# power.net
KiCad netlist of a schematic drawn in Altium Designer
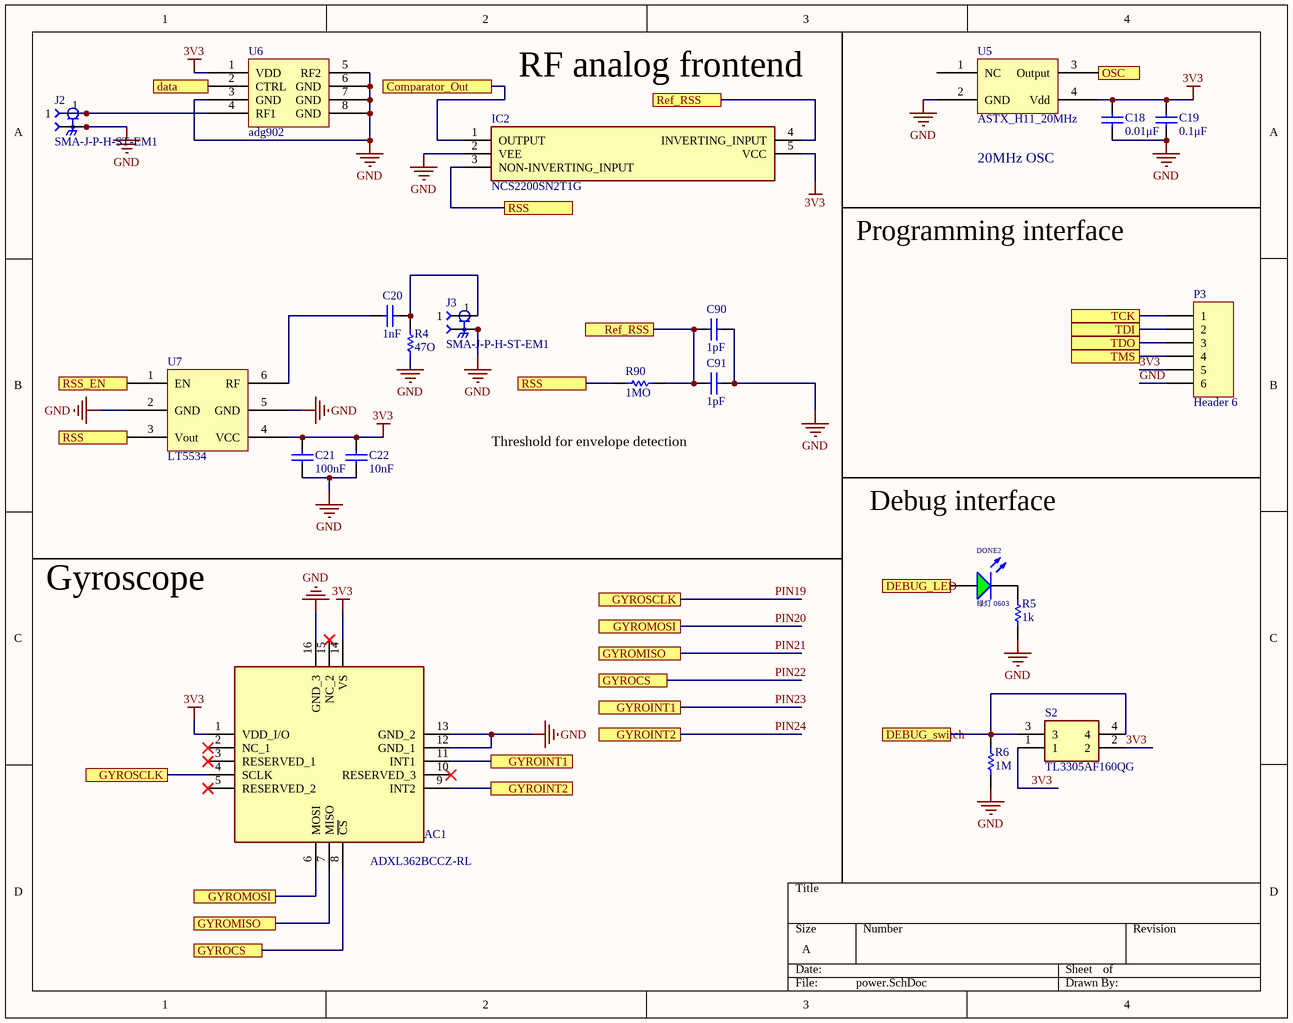
[diagram p0: power.SchDoc]

(export (version "E")
  (design (tool "Eeschema 10.0.6"))
  (components
    (comp (ref "AC1")
      (value "ADXL362BCCZ-RL")
      (footprint "SamacSys:ADXL362BCCZRL")
      (description "Accelerometer")
      (fields (field (name "MOUSER2 PART NUMBER") "584-ADXL362BCCZ-R"))
      (libsource (lib "*") (part "ADXL362BCCZ-RL"))
    )
    (comp (ref "C18")
      (value "0.01μF")
      (footprint "1608[0603]")
      (description "MLCCs")
      (fields (field (name "PUBLISHER") "Altium Limited"))
      (libsource (lib "Passer") (part "CAP_3"))
    )
    (comp (ref "C19")
      (value "0.1μF")
      (footprint "1608[0603]")
      (description "MLCCs")
      (fields (field (name "PUBLISHER") "Altium Limited"))
      (libsource (lib "Passer") (part "CAP_2"))
    )
    (comp (ref "C20")
      (value "1nF")
      (footprint "1608[0603]")
      (description "Ceramic Capacitor (Surface Mount)")
      (fields (field (name "MANUFACTURER") "Generic Ceramic Chip Cap (TBD)"))
      (libsource (lib "wisp") (part "Cap"))
    )
    (comp (ref "C21")
      (value "100nF")
      (footprint "1608[0603]")
      (description "Ceramic Capacitor (Surface Mount)")
      (fields (field (name "MANUFACTURER") "Generic Ceramic Chip Cap (TBD)"))
      (libsource (lib "wisp") (part "Cap"))
    )
    (comp (ref "C22")
      (value "10nF")
      (footprint "1608[0603]")
      (description "Ceramic Capacitor (Surface Mount)")
      (fields (field (name "MANUFACTURER") "Generic Ceramic Chip Cap (TBD)"))
      (libsource (lib "wisp") (part "Cap"))
    )
    (comp (ref "C90")
      (value "1pF")
      (footprint "1608[0603]")
      (description "Ceramic Capacitor (Surface Mount)")
      (fields (field (name "MANUFACTURER") "Generic Ceramic Chip Cap (TBD)") (field (name "Comment") "1nF"))
      (libsource (lib "wisp") (part "Cap"))
    )
    (comp (ref "C91")
      (value "1pF")
      (footprint "1608[0603]")
      (description "Ceramic Capacitor (Surface Mount)")
      (fields (field (name "MANUFACTURER") "Generic Ceramic Chip Cap (TBD)") (field (name "Comment") "1nF"))
      (libsource (lib "wisp") (part "Cap"))
    )
    (comp (ref "DONE2")
      (value "绿灯 0603")
      (footprint "0603_LED")
      (description "发光二极管")
      (libsource (lib "Passer") (part "0603 绿灯"))
    )
    (comp (ref "IC2")
      (value "NCS2200SN2T1G")
      (footprint "SamacSys:SOT95P275X110-5N")
      (description "Integrated Circuit")
      (libsource (lib "ComparatorLib") (part "NCS2200SN2T1G"))
    )
    (comp (ref "J2")
      (value "SMA-J-P-H-ST-EM1")
      (footprint "SAMTEC_SMA-J-P-H-ST-EM1")
      (description "SMA Connector Jack, Female Socket 50Ohm Board Edge, End Launch Solder")
      (fields (field (name "MF") "Samtec") (field (name "DIGI-KEY_PART_NUMBER") "SAM8857-ND"))
      (libsource (lib "SMA-J-P-H-ST-EM1") (part "SMA-J-P-H-ST-EM1"))
    )
    (comp (ref "J3")
      (value "SMA-J-P-H-ST-EM1")
      (footprint "SAMTEC_SMA-J-P-H-ST-EM1")
      (description "SMA Connector Jack, Female Socket 50Ohm Board Edge, End Launch Solder")
      (fields (field (name "MF") "Samtec") (field (name "DIGI-KEY_PART_NUMBER") "SAM8857-ND"))
      (libsource (lib "SMA-J-P-H-ST-EM1") (part "SMA-J-P-H-ST-EM1"))
    )
    (comp (ref "P3")
      (value "Header 6")
      (footprint "HDR1X6")
      (description "Header, 6-Pin")
      (fields (field (name "PUBLISHER") "Altium Limited"))
      (libsource (lib "Miscellaneous Connectors") (part "Header 6"))
    )
    (comp (ref "R4")
      (value "47O")
      (footprint "1608[0603]")
      (description "Chip Resistor (Surface Mount)")
      (fields (field (name "MANUFACTURER") "Generic Chip Res (TBD)") (field (name "Comment") "47 Ohm"))
      (libsource (lib "wisp") (part "Res"))
    )
    (comp (ref "R5")
      (value "1k")
      (footprint "1608[0603]")
      (description "Chip Resistor (Surface Mount)")
      (fields (field (name "MANUFACTURER") "Generic Chip Res (TBD)") (field (name "Comment") "1k Ohm"))
      (libsource (lib "wisp") (part "Res"))
    )
    (comp (ref "R6")
      (value "1M")
      (footprint "1608[0603]")
      (description "Chip Resistor (Surface Mount)")
      (fields (field (name "MANUFACTURER") "Generic Chip Res (TBD)") (field (name "Comment") "1k Ohm"))
      (libsource (lib "wisp") (part "Res"))
    )
    (comp (ref "R90")
      (value "1MO")
      (footprint "1608[0603]")
      (description "Chip Resistor (Surface Mount)")
      (fields (field (name "MANUFACTURER") "Generic Chip Res (TBD)") (field (name "Comment") "47 Ohm"))
      (libsource (lib "wisp") (part "Res"))
    )
    (comp (ref "S2")
      (value "TL3305AF160QG")
      (footprint "TL3305AF160QG")
      (description "Switch")
      (fields (field (name "MOUSER2 PART NUMBER") "612-TL3305AF160QG"))
      (libsource (lib "*") (part "TL3305AF160QG"))
    )
    (comp (ref "U5")
      (value "ASTX_H11_20MHz")
      (footprint "ASTX_H11")
      (libsource (lib "pengyulib") (part "ASTX_H11_20MHz"))
    )
    (comp (ref "U6") (value "adg902") (footprint "ADG902") (libsource (lib "pengyulib") (part "adg902")))
    (comp (ref "U7") (value "LT5534") (footprint "LT5534") (libsource (lib "pengyulib") (part "LT55534")))
  )
  (nets
    (net (code "1") (name "/Comparator_Out") (class "Default")
      (node (ref "IC2") (pin "1") (pinfunction "OUTPUT_1") (pintype "passive"))
    )
    (net (code "2") (name "/DEBUG_LED") (class "Default")
      (node (ref "DONE2") (pin "A") (pinfunction "A_A") (pintype "passive"))
    )
    (net (code "3") (name "/DEBUG_switch") (class "Default")
      (node (ref "R6") (pin "2") (pinfunction "2_2") (pintype "passive"))
      (node (ref "S2") (pin "3") (pinfunction "3_3") (pintype "passive"))
      (node (ref "S2") (pin "4") (pinfunction "4_4") (pintype "passive"))
    )
    (net (code "4") (name "/OSC") (class "Default")
      (node (ref "U5") (pin "3") (pinfunction "Output_3") (pintype "passive"))
    )
    (net (code "5") (name "/PIN19") (class "Default")
      (node (ref "AC1") (pin "4") (pinfunction "SCLK_4") (pintype "passive"))
    )
    (net (code "6") (name "/PIN20") (class "Default")
      (node (ref "AC1") (pin "6") (pinfunction "MOSI_6") (pintype "passive"))
    )
    (net (code "7") (name "/PIN21") (class "Default")
      (node (ref "AC1") (pin "7") (pinfunction "MISO_7") (pintype "passive"))
    )
    (net (code "8") (name "/PIN22") (class "Default")
      (node (ref "AC1") (pin "8") (pinfunction "~{CS}_8") (pintype "passive"))
    )
    (net (code "9") (name "/PIN23") (class "Default")
      (node (ref "AC1") (pin "11") (pinfunction "INT1_11") (pintype "passive"))
    )
    (net (code "10") (name "/PIN24") (class "Default")
      (node (ref "AC1") (pin "9") (pinfunction "INT2_9") (pintype "passive"))
    )
    (net (code "11") (name "/RSS") (class "Default")
      (node (ref "IC2") (pin "3") (pinfunction "NON-INVERTING_INPUT_3") (pintype "passive"))
      (node (ref "R90") (pin "2") (pinfunction "2_2") (pintype "passive"))
      (node (ref "U7") (pin "3") (pinfunction "Vout_3") (pintype "passive"))
    )
    (net (code "12") (name "/RSS_EN") (class "Default")
      (node (ref "U7") (pin "1") (pinfunction "EN_1") (pintype "passive"))
    )
    (net (code "13") (name "/Ref_RSS") (class "Default")
      (node (ref "C90") (pin "1") (pinfunction "1_1") (pintype "passive"))
      (node (ref "C91") (pin "1") (pinfunction "1_1") (pintype "passive"))
      (node (ref "IC2") (pin "4") (pinfunction "INVERTING_INPUT_4") (pintype "passive"))
      (node (ref "R90") (pin "1") (pinfunction "1_1") (pintype "passive"))
    )
    (net (code "14") (name "/TCK") (class "Default")
      (node (ref "P3") (pin "1") (pinfunction "1_1") (pintype "passive"))
    )
    (net (code "15") (name "/TDI") (class "Default")
      (node (ref "P3") (pin "2") (pinfunction "2_2") (pintype "passive"))
    )
    (net (code "16") (name "/TDO") (class "Default")
      (node (ref "P3") (pin "3") (pinfunction "3_3") (pintype "passive"))
    )
    (net (code "17") (name "/TMS") (class "Default")
      (node (ref "P3") (pin "4") (pinfunction "4_4") (pintype "passive"))
    )
    (net (code "18") (name "/data") (class "Default")
      (node (ref "U6") (pin "2") (pinfunction "CTRL_2") (pintype "passive"))
    )
    (net (code "19") (name "3V3") (class "Default")
      (node (ref "AC1") (pin "1") (pinfunction "VDD_I/O_1") (pintype "passive"))
      (node (ref "AC1") (pin "14") (pinfunction "VS_14") (pintype "passive"))
      (node (ref "C18") (pin "2") (pinfunction "2_2") (pintype "passive"))
      (node (ref "C19") (pin "2") (pinfunction "2_2") (pintype "passive"))
      (node (ref "C21") (pin "2") (pinfunction "2_2") (pintype "passive"))
      (node (ref "C22") (pin "2") (pinfunction "2_2") (pintype "passive"))
      (node (ref "IC2") (pin "5") (pinfunction "VCC_5") (pintype "passive"))
      (node (ref "P3") (pin "5") (pinfunction "5_5") (pintype "passive"))
      (node (ref "S2") (pin "1") (pinfunction "1_1") (pintype "passive"))
      (node (ref "S2") (pin "2") (pinfunction "2_2") (pintype "passive"))
      (node (ref "U5") (pin "4") (pinfunction "Vdd_4") (pintype "passive"))
      (node (ref "U6") (pin "1") (pinfunction "VDD_1") (pintype "passive"))
      (node (ref "U7") (pin "4") (pinfunction "VCC_4") (pintype "passive"))
    )
    (net (code "20") (name "GND") (class "Default")
      (node (ref "AC1") (pin "12") (pinfunction "GND_1_12") (pintype "passive"))
      (node (ref "AC1") (pin "13") (pinfunction "GND_2_13") (pintype "passive"))
      (node (ref "AC1") (pin "16") (pinfunction "GND_3_16") (pintype "passive"))
      (node (ref "C18") (pin "1") (pinfunction "1_1") (pintype "passive"))
      (node (ref "C19") (pin "1") (pinfunction "1_1") (pintype "passive"))
      (node (ref "C21") (pin "1") (pinfunction "1_1") (pintype "passive"))
      (node (ref "C22") (pin "1") (pinfunction "1_1") (pintype "passive"))
      (node (ref "C90") (pin "2") (pinfunction "2_2") (pintype "passive"))
      (node (ref "C91") (pin "2") (pinfunction "2_2") (pintype "passive"))
      (node (ref "IC2") (pin "2") (pinfunction "VEE_2") (pintype "passive"))
      (node (ref "J2") (pin "2_1") (pinfunction "2_2_1") (pintype "passive"))
      (node (ref "J2") (pin "2_2") (pinfunction "2_2_2") (pintype "passive"))
      (node (ref "J2") (pin "3_1") (pinfunction "2_3_1") (pintype "passive"))
      (node (ref "J2") (pin "3_2") (pinfunction "2_3_2") (pintype "passive"))
      (node (ref "J3") (pin "2_1") (pinfunction "2_2_1") (pintype "passive"))
      (node (ref "J3") (pin "2_2") (pinfunction "2_2_2") (pintype "passive"))
      (node (ref "J3") (pin "3_1") (pinfunction "2_3_1") (pintype "passive"))
      (node (ref "J3") (pin "3_2") (pinfunction "2_3_2") (pintype "passive"))
      (node (ref "P3") (pin "6") (pinfunction "6_6") (pintype "passive"))
      (node (ref "R4") (pin "1") (pinfunction "1_1") (pintype "passive"))
      (node (ref "R5") (pin "1") (pinfunction "1_1") (pintype "passive"))
      (node (ref "R6") (pin "1") (pinfunction "1_1") (pintype "passive"))
      (node (ref "U5") (pin "2") (pinfunction "GND_2") (pintype "passive"))
      (node (ref "U6") (pin "3") (pinfunction "GND_3") (pintype "passive"))
      (node (ref "U6") (pin "5") (pinfunction "RF2_5") (pintype "passive"))
      (node (ref "U6") (pin "6") (pinfunction "GND_6") (pintype "passive"))
      (node (ref "U6") (pin "7") (pinfunction "GND_7") (pintype "passive"))
      (node (ref "U6") (pin "8") (pinfunction "GND_8") (pintype "passive"))
      (node (ref "U7") (pin "2") (pinfunction "GND_2") (pintype "passive"))
      (node (ref "U7") (pin "5") (pinfunction "GND_5") (pintype "passive"))
    )
    (net (code "21") (name "Net-(C20-Pad2)") (class "Default")
      (node (ref "C20") (pin "2") (pinfunction "2_2") (pintype "passive"))
      (node (ref "J3") (pin "1") (pinfunction "1_1") (pintype "passive"))
      (node (ref "R4") (pin "2") (pinfunction "2_2") (pintype "passive"))
    )
    (net (code "22") (name "Net-(DONE2-PadK)") (class "Default")
      (node (ref "DONE2") (pin "K") (pinfunction "K_K") (pintype "passive"))
      (node (ref "R5") (pin "2") (pinfunction "2_2") (pintype "passive"))
    )
    (net (code "23") (name "Net-(U6-RF1)") (class "Default")
      (node (ref "J2") (pin "1") (pinfunction "1_1") (pintype "passive"))
      (node (ref "U6") (pin "4") (pinfunction "RF1_4") (pintype "passive"))
    )
    (net (code "24") (name "Net-(U7-RF)") (class "Default")
      (node (ref "C20") (pin "1") (pinfunction "1_1") (pintype "passive"))
      (node (ref "U7") (pin "6") (pinfunction "RF_6") (pintype "passive"))
    )
    (net (code "25") (name "unconnected-(AC1-NC_1-Pad2)") (class "Default")
      (node (ref "AC1") (pin "2") (pinfunction "NC_1_2") (pintype "passive+no_connect"))
    )
    (net (code "26") (name "unconnected-(AC1-NC_2-Pad15)") (class "Default")
      (node (ref "AC1") (pin "15") (pinfunction "NC_2_15") (pintype "passive+no_connect"))
    )
    (net (code "27") (name "unconnected-(AC1-RESERVED_1-Pad3)") (class "Default")
      (node (ref "AC1") (pin "3") (pinfunction "RESERVED_1_3") (pintype "passive+no_connect"))
    )
    (net (code "28") (name "unconnected-(AC1-RESERVED_2-Pad5)") (class "Default")
      (node (ref "AC1") (pin "5") (pinfunction "RESERVED_2_5") (pintype "passive+no_connect"))
    )
    (net (code "29") (name "unconnected-(AC1-RESERVED_3-Pad10)") (class "Default")
      (node (ref "AC1") (pin "10") (pinfunction "RESERVED_3_10") (pintype "passive+no_connect"))
    )
    (net (code "30") (name "unconnected-(U5-NC-Pad1)") (class "Default")
      (node (ref "U5") (pin "1") (pinfunction "NC_1") (pintype "passive"))
    )
  )
)
